# openx3.net
KiCad netlist of a schematic drawn in EAGLE
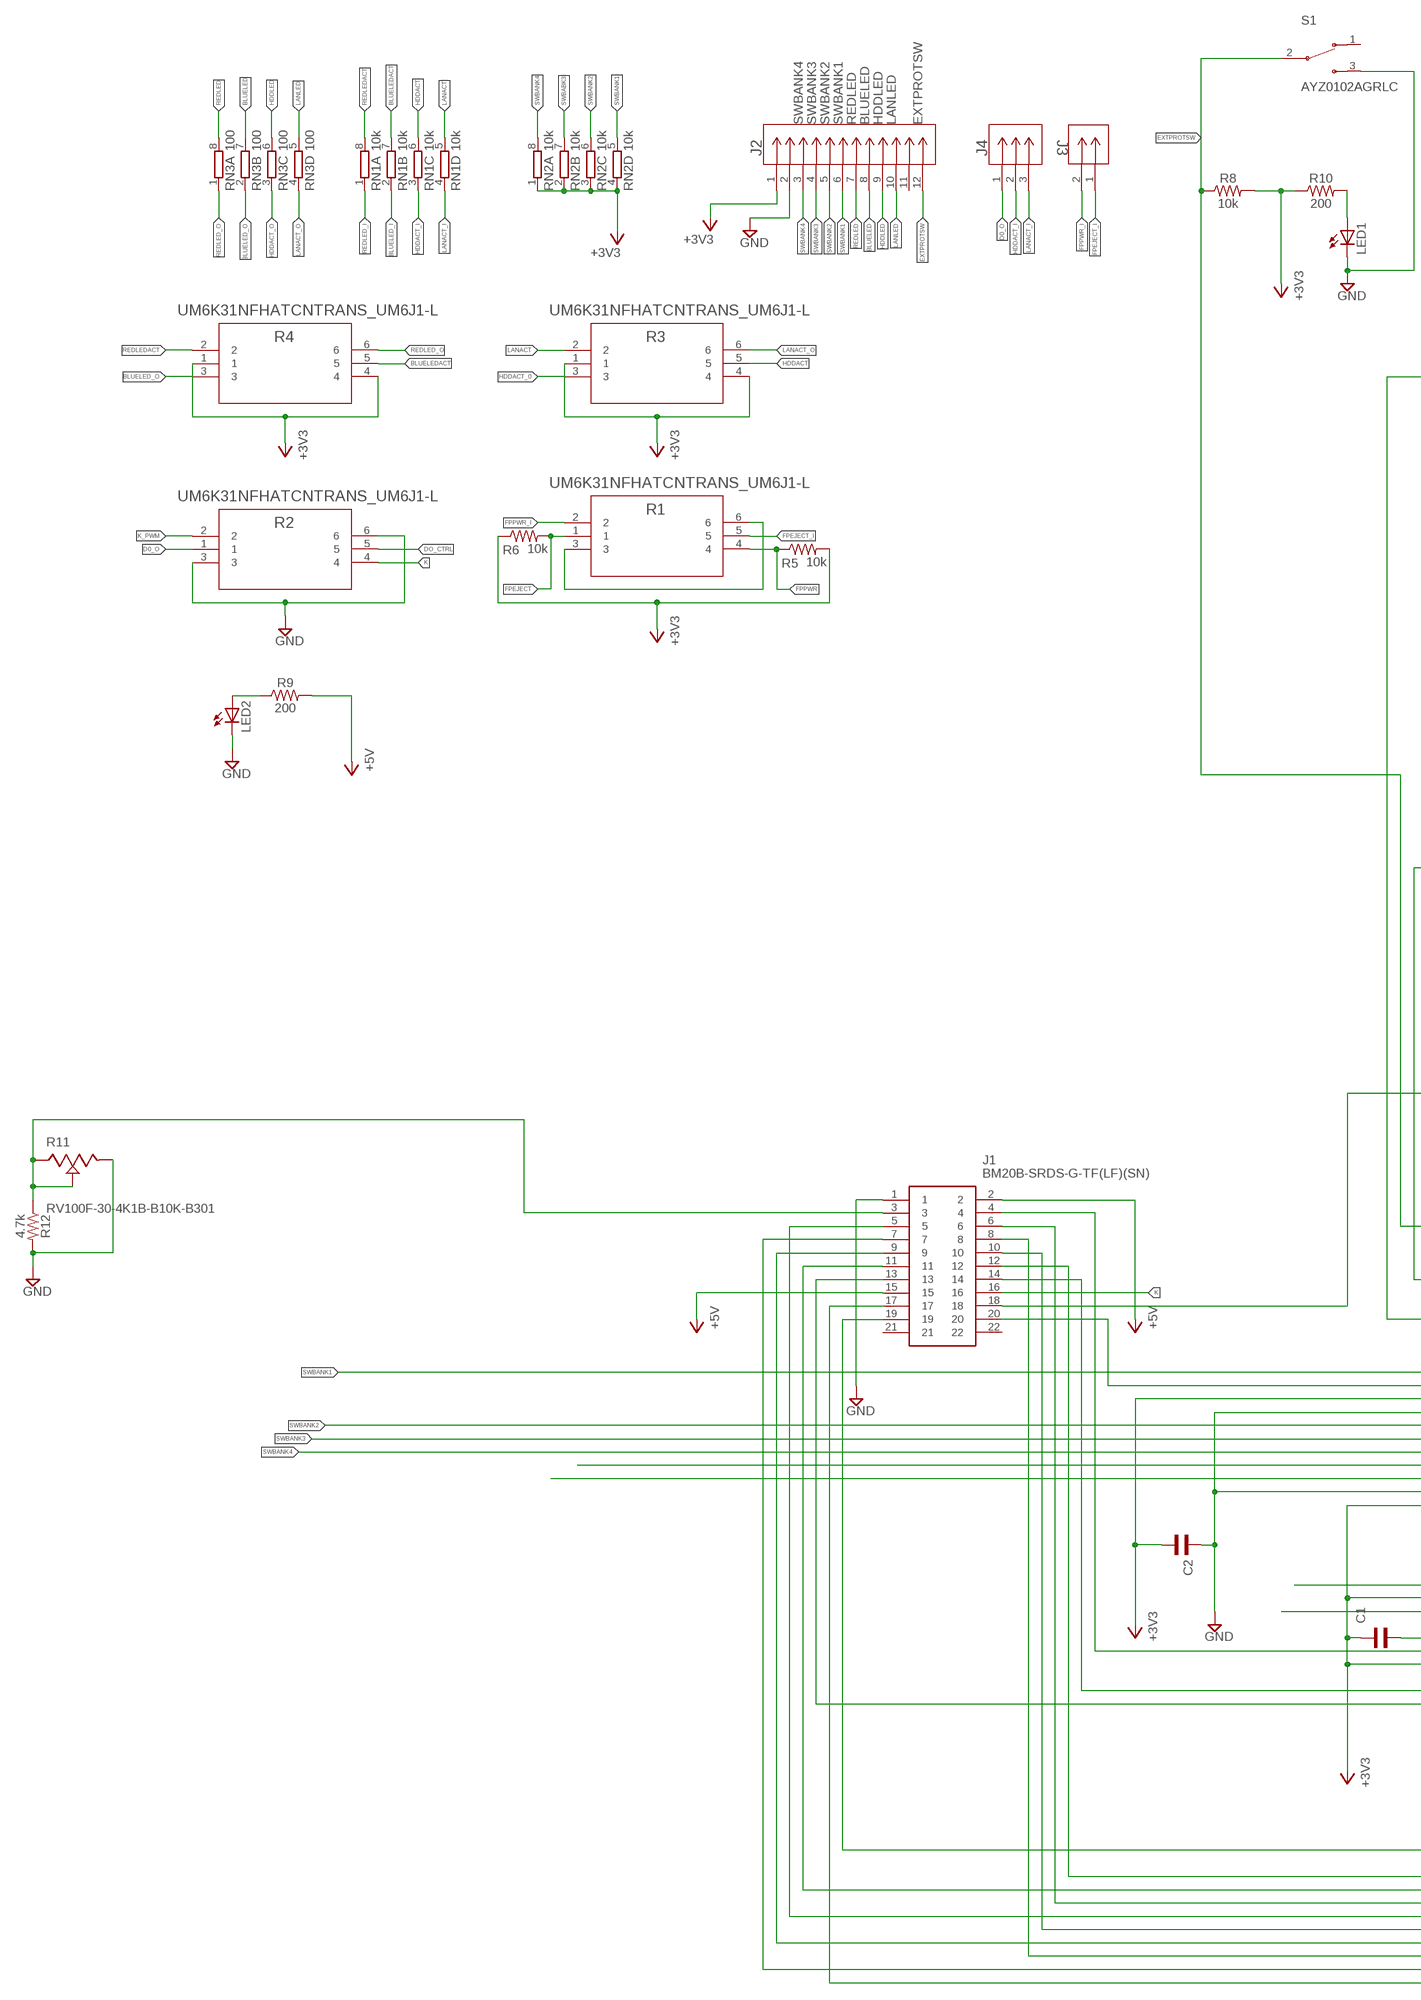
[diagram p0: schematic, sheet 1, part 1 of 2]
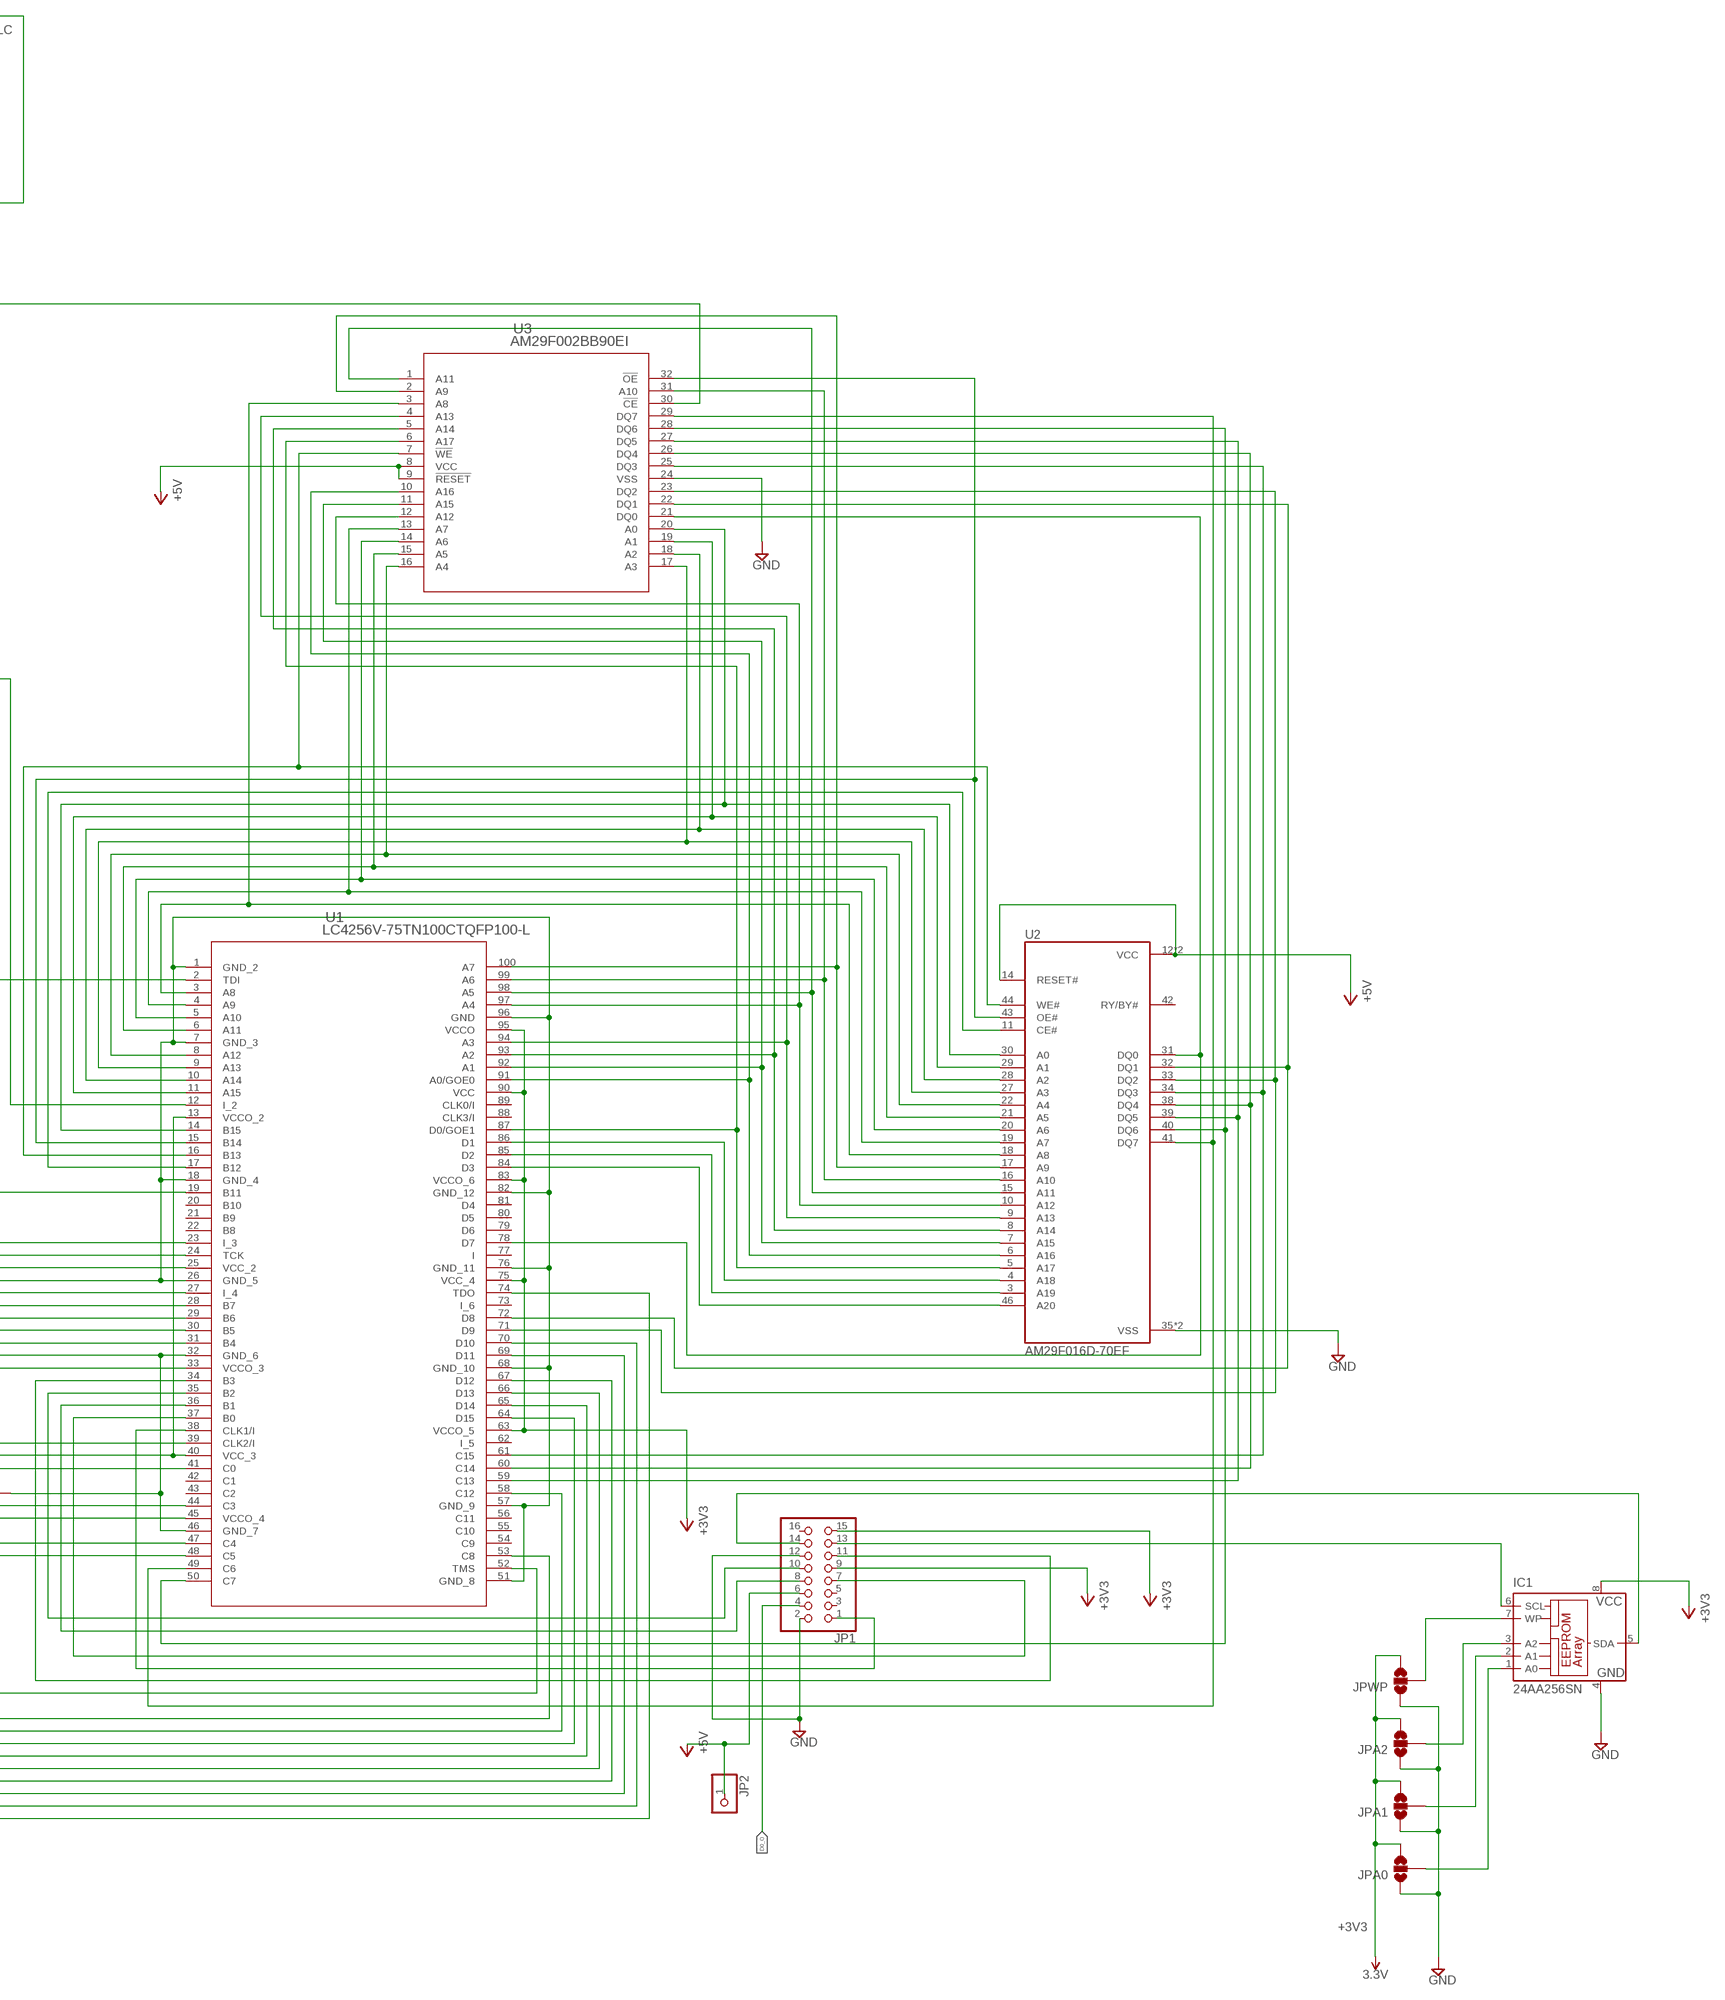
[diagram p1: schematic, sheet 1, part 2 of 2]

(export (version "E")
  (design (tool "Eeschema 10.0.6"))
  (components
    (comp (ref "C1")
      (value "WCAP-CSGP_0603_885012006001_REFLOW")
      (footprint "eagle-import:WCAP-CSGP_0603_REFLOW")
      (libsource (lib "eagle-import") (part "WCAP-CSGP_0603_REFLOW_885012006001"))
    )
    (comp (ref "C2")
      (value "WCAP-CSGP_0603_885012006001_REFLOW")
      (footprint "eagle-import:WCAP-CSGP_0603_REFLOW")
      (libsource (lib "eagle-import") (part "WCAP-CSGP_0603_REFLOW_885012006001"))
    )
    (comp (ref "IC1")
      (value "24AA256SN")
      (footprint "eagle-import:SO-08")
      (fields (field (name "MPN") "24AA256T-I/SM"))
      (libsource (lib "eagle-import") (part "24SNAA256"))
    )
    (comp (ref "J1")
      (value "BM20B-SRDS-G-TF(LF)(SN)")
      (footprint "eagle-import:BM20BSRDSGTFLFSN")
      (libsource (lib "eagle-import") (part "BM20B-SRDS-G-TF(LF)(SN)"))
    )
    (comp (ref "J2")
      (value "SM12B-SRSS-TB(LF)(SN)")
      (footprint "eagle-import:CONN_SM12B-SRSS-TB(LF)(SN)")
      (fields (field (name "COPYRIGHT") "Copyright (C) 2018 Accelerated Designs. All rights reserved"))
      (libsource (lib "eagle-import") (part "SM12B-SRSS-TB(LF)(SN)"))
    )
    (comp (ref "J3")
      (value "53398-0271")
      (footprint "eagle-import:CON00327_2")
      (fields (field (name "COPYRIGHT") "Copyright (C) 2016 Accelerated Designs. All rights reserved"))
      (libsource (lib "eagle-import") (part "53398-0271"))
    )
    (comp (ref "J4")
      (value "1734260-3")
      (footprint "eagle-import:CON3_1X3_DRM125_HPI")
      (libsource (lib "eagle-import") (part "1734260-3"))
    )
    (comp (ref "JP1")
      (value "PINHD-2X8")
      (footprint "eagle-import:2X08")
      (libsource (lib "eagle-import") (part "PINHD-2X8"))
    )
    (comp (ref "JP2")
      (value "PINHD-1X1")
      (footprint "eagle-import:1X01")
      (libsource (lib "eagle-import") (part "PINHD-1X1"))
    )
    (comp (ref "JPA0")
      (value "JUMPER-SMT_3_NO_NO-SILK")
      (footprint "eagle-import:SMT-JUMPER_3_NO_NO-SILK")
      (libsource (lib "eagle-import") (part "JUMPER-SMT_3_NO_NO-SILK"))
    )
    (comp (ref "JPA1")
      (value "JUMPER-SMT_3_NO_NO-SILK")
      (footprint "eagle-import:SMT-JUMPER_3_NO_NO-SILK")
      (libsource (lib "eagle-import") (part "JUMPER-SMT_3_NO_NO-SILK"))
    )
    (comp (ref "JPA2")
      (value "JUMPER-SMT_3_NO_NO-SILK")
      (footprint "eagle-import:SMT-JUMPER_3_NO_NO-SILK")
      (libsource (lib "eagle-import") (part "JUMPER-SMT_3_NO_NO-SILK"))
    )
    (comp (ref "JPWP")
      (value "JUMPER-SMT_3_NO_NO-SILK")
      (footprint "eagle-import:SMT-JUMPER_3_NO_NO-SILK")
      (libsource (lib "eagle-import") (part "JUMPER-SMT_3_NO_NO-SILK"))
    )
    (comp (ref "LED1")
      (value "LEDCHIPLED_0805")
      (footprint "eagle-import:CHIPLED_0805")
      (libsource (lib "eagle-import") (part "LEDCHIPLED_0805"))
    )
    (comp (ref "LED2")
      (value "LEDCHIPLED_0805")
      (footprint "eagle-import:CHIPLED_0805")
      (libsource (lib "eagle-import") (part "LEDCHIPLED_0805"))
    )
    (comp (ref "R1")
      (value "UM6K31NFHATCNTRANS_UM6J1-L")
      (footprint "eagle-import:TRANS_UM6J1-L")
      (fields
        (field (name "MANUFACTURER_PART_NUMBER") "UM6K31NFHATCN")
        (field (name "COPYRIGHT") "Copyright (C) 2018 Accelerated Designs. All rights reserved")
      )
      (libsource (lib "eagle-import") (part "UM6K31NFHATCNTRANS_UM6J1-L"))
    )
    (comp (ref "R2")
      (value "UM6K31NFHATCNTRANS_UM6J1-L")
      (footprint "eagle-import:TRANS_UM6J1-L")
      (fields
        (field (name "MANUFACTURER_PART_NUMBER") "UM6K31NFHATCN")
        (field (name "COPYRIGHT") "Copyright (C) 2018 Accelerated Designs. All rights reserved")
      )
      (libsource (lib "eagle-import") (part "UM6K31NFHATCNTRANS_UM6J1-L"))
    )
    (comp (ref "R3")
      (value "UM6K31NFHATCNTRANS_UM6J1-L")
      (footprint "eagle-import:TRANS_UM6J1-L")
      (fields
        (field (name "MANUFACTURER_PART_NUMBER") "UM6K31NFHATCN")
        (field (name "COPYRIGHT") "Copyright (C) 2018 Accelerated Designs. All rights reserved")
      )
      (libsource (lib "eagle-import") (part "UM6K31NFHATCNTRANS_UM6J1-L"))
    )
    (comp (ref "R4")
      (value "UM6K31NFHATCNTRANS_UM6J1-L")
      (footprint "eagle-import:TRANS_UM6J1-L")
      (fields
        (field (name "MANUFACTURER_PART_NUMBER") "UM6K31NFHATCN")
        (field (name "COPYRIGHT") "Copyright (C) 2018 Accelerated Designs. All rights reserved")
      )
      (libsource (lib "eagle-import") (part "UM6K31NFHATCNTRANS_UM6J1-L"))
    )
    (comp (ref "R5")
      (value "10k")
      (footprint "eagle-import:0603")
      (libsource (lib "eagle-import") (part "10KOHM-0603-1/10W-1%"))
    )
    (comp (ref "R6")
      (value "10k")
      (footprint "eagle-import:0603")
      (libsource (lib "eagle-import") (part "10KOHM-0603-1/10W-1%"))
    )
    (comp (ref "R8")
      (value "10k")
      (footprint "eagle-import:0603")
      (libsource (lib "eagle-import") (part "10KOHM-0603-1/10W-1%"))
    )
    (comp (ref "R9")
      (value "200")
      (footprint "eagle-import:0603")
      (libsource (lib "eagle-import") (part "200OHM-0603-1/10W-1%"))
    )
    (comp (ref "R10")
      (value "200")
      (footprint "eagle-import:0603")
      (libsource (lib "eagle-import") (part "200OHM-0603-1/10W-1%"))
    )
    (comp (ref "R11")
      (value "RV100F-30-4K1B-B10K-B301")
      (footprint "eagle-import:TRIM_RV100F-30-4K1B-B10K-B301")
      (fields (field (name "MF") "Alpha Taiwan"))
      (libsource (lib "eagle-import") (part "RV100F-30-4K1B-B10K-B301"))
    )
    (comp (ref "R12")
      (value "4.7k")
      (footprint "eagle-import:0603")
      (libsource (lib "eagle-import") (part "4.7KOHM-0603-1/10W-1%"))
    )
    (comp (ref "RN1")
      (value "10k")
      (footprint "eagle-import:0603-ARV")
      (libsource (lib "eagle-import") (part "4R-N0603-ARV"))
    )
    (comp (ref "RN2")
      (value "10k")
      (footprint "eagle-import:0603-ARV")
      (libsource (lib "eagle-import") (part "4R-N0603-ARV"))
    )
    (comp (ref "RN3")
      (value "100")
      (footprint "eagle-import:0603-ARV")
      (libsource (lib "eagle-import") (part "4R-N0603-ARV"))
    )
    (comp (ref "S1")
      (value "AYZ0102AGRLC")
      (footprint "eagle-import:SW_AYZ0102AGRLC")
      (fields (field (name "MF") "C&K"))
      (libsource (lib "eagle-import") (part "AYZ0102AGRLC"))
    )
    (comp (ref "U1")
      (value "LC4256V-75TN100CTQFP100-L")
      (footprint "eagle-import:TQFP100-L")
      (fields (field (name "MANUFACTURER_PART_NUMBER") "LC4256V-75TN100C"))
      (libsource (lib "eagle-import") (part "LC4256V-75TN100CTQFP100-L"))
    )
    (comp (ref "U2")
      (value "AM29F016D-70EF")
      (footprint "eagle-import:SOP50P2000X120-48N")
      (fields (field (name "MF") "Spansion"))
      (libsource (lib "eagle-import") (part "AM29F016D-70EF"))
    )
    (comp (ref "U3")
      (value "AM29F002BB90EI")
      (footprint "eagle-import:TS032")
      (libsource (lib "eagle-import") (part "AM29F002BB90EI"))
    )
  )
  (nets
    (net (code "1") (name "+3V3") (class "Default")
      (node (ref "C1") (pin "2") (pinfunction "2_2") (pintype "passive"))
      (node (ref "C2") (pin "1") (pinfunction "1_1") (pintype "passive"))
      (node (ref "IC1") (pin "8") (pinfunction "VCC_8") (pintype "power_in"))
      (node (ref "J2") (pin "1") (pinfunction "1_1") (pintype "passive"))
      (node (ref "JP1") (pin "15") (pinfunction "15_15") (pintype "passive"))
      (node (ref "JP1") (pin "9") (pinfunction "9_9") (pintype "passive"))
      (node (ref "JPA0") (pin "3") (pinfunction "3_3") (pintype "passive"))
      (node (ref "JPA1") (pin "3") (pinfunction "3_3") (pintype "passive"))
      (node (ref "JPA2") (pin "3") (pinfunction "3_3") (pintype "passive"))
      (node (ref "JPWP") (pin "3") (pinfunction "3_3") (pintype "passive"))
      (node (ref "R10") (pin "1") (pinfunction "1_1") (pintype "passive"))
      (node (ref "R3") (pin "1") (pinfunction "1_1") (pintype "passive"))
      (node (ref "R3") (pin "4") (pinfunction "4_4") (pintype "passive"))
      (node (ref "R4") (pin "1") (pinfunction "1_1") (pintype "passive"))
      (node (ref "R4") (pin "4") (pinfunction "4_4") (pintype "passive"))
      (node (ref "R5") (pin "2") (pinfunction "2_2") (pintype "passive"))
      (node (ref "R6") (pin "1") (pinfunction "1_1") (pintype "passive"))
      (node (ref "R8") (pin "2") (pinfunction "2_2") (pintype "passive"))
      (node (ref "RN2") (pin "1") (pinfunction "1_1") (pintype "passive"))
      (node (ref "RN2") (pin "2") (pinfunction "1_2") (pintype "passive"))
      (node (ref "RN2") (pin "3") (pinfunction "1_3") (pintype "passive"))
      (node (ref "RN2") (pin "4") (pinfunction "1_4") (pintype "passive"))
      (node (ref "U1") (pin "13") (pinfunction "VCCO_2_13") (pintype "power_in"))
      (node (ref "U1") (pin "25") (pinfunction "VCC_2_25") (pintype "power_in"))
      (node (ref "U1") (pin "33") (pinfunction "VCCO_3_33") (pintype "power_in"))
      (node (ref "U1") (pin "40") (pinfunction "VCC_3_40") (pintype "power_in"))
      (node (ref "U1") (pin "45") (pinfunction "VCCO_4_45") (pintype "power_in"))
      (node (ref "U1") (pin "63") (pinfunction "VCCO_5_63") (pintype "power_in"))
      (node (ref "U1") (pin "75") (pinfunction "VCC_4_75") (pintype "power_in"))
      (node (ref "U1") (pin "83") (pinfunction "VCCO_6_83") (pintype "power_in"))
      (node (ref "U1") (pin "90") (pinfunction "VCC_90") (pintype "power_in"))
      (node (ref "U1") (pin "95") (pinfunction "VCCO_95") (pintype "power_in"))
    )
    (net (code "2") (name "+5V") (class "Default")
      (node (ref "J1") (pin "15") (pinfunction "15_15") (pintype "bidirectional"))
      (node (ref "J1") (pin "2") (pinfunction "2_2") (pintype "bidirectional"))
      (node (ref "JP1") (pin "6") (pinfunction "6_6") (pintype "passive"))
      (node (ref "JP2") (pin "1") (pinfunction "1_1") (pintype "passive"))
      (node (ref "R9") (pin "2") (pinfunction "2_2") (pintype "passive"))
      (node (ref "U2") (pin "12") (pinfunction "VCC_12") (pintype "power_in"))
      (node (ref "U2") (pin "14") (pinfunction "RESET#_14") (pintype "input"))
      (node (ref "U2") (pin "37") (pinfunction "VCC_37") (pintype "power_in"))
      (node (ref "U3") (pin "8") (pinfunction "VCC_8") (pintype "power_in"))
      (node (ref "U3") (pin "9") (pinfunction "~{RESET}_9") (pintype "input"))
    )
    (net (code "3") (name "BLUELED") (class "Default")
      (node (ref "J2") (pin "8") (pinfunction "8_8") (pintype "passive"))
      (node (ref "RN3") (pin "7") (pinfunction "2_7") (pintype "passive"))
    )
    (net (code "4") (name "BLUELEDACT") (class "Default")
      (node (ref "R4") (pin "5") (pinfunction "5_5") (pintype "passive"))
      (node (ref "RN1") (pin "7") (pinfunction "2_7") (pintype "passive"))
    )
    (net (code "5") (name "BLUELED_I") (class "Default")
      (node (ref "RN1") (pin "2") (pinfunction "1_2") (pintype "passive"))
    )
    (net (code "6") (name "BLUELED_O") (class "Default")
      (node (ref "R4") (pin "3") (pinfunction "3_3") (pintype "passive"))
      (node (ref "RN3") (pin "2") (pinfunction "1_2") (pintype "passive"))
    )
    (net (code "7") (name "D0_O") (class "Default")
      (node (ref "J4") (pin "1") (pinfunction "1_1") (pintype "passive"))
      (node (ref "JP1") (pin "4") (pinfunction "4_4") (pintype "passive"))
      (node (ref "R2") (pin "1") (pinfunction "1_1") (pintype "passive"))
    )
    (net (code "8") (name "DO_CTRL") (class "Default")
      (node (ref "R2") (pin "5") (pinfunction "5_5") (pintype "passive"))
    )
    (net (code "9") (name "EXTPROTSW") (class "Default")
      (node (ref "J2") (pin "12") (pinfunction "12_12") (pintype "passive"))
      (node (ref "R8") (pin "1") (pinfunction "1_1") (pintype "passive"))
      (node (ref "S1") (pin "2") (pinfunction "2_2") (pintype "passive"))
      (node (ref "U1") (pin "12") (pinfunction "I_2_12") (pintype "passive"))
    )
    (net (code "10") (name "FPEJECT") (class "Default")
      (node (ref "R1") (pin "1") (pinfunction "1_1") (pintype "passive"))
      (node (ref "R6") (pin "2") (pinfunction "2_2") (pintype "passive"))
    )
    (net (code "11") (name "FPEJECT_I") (class "Default")
      (node (ref "J3") (pin "1") (pinfunction "1_1") (pintype "passive"))
      (node (ref "R1") (pin "5") (pinfunction "5_5") (pintype "passive"))
    )
    (net (code "12") (name "FPPWR") (class "Default")
      (node (ref "R1") (pin "4") (pinfunction "4_4") (pintype "passive"))
      (node (ref "R5") (pin "1") (pinfunction "1_1") (pintype "passive"))
    )
    (net (code "13") (name "FPPWR_I") (class "Default")
      (node (ref "J3") (pin "2") (pinfunction "2_2") (pintype "passive"))
      (node (ref "R1") (pin "2") (pinfunction "2_2") (pintype "passive"))
    )
    (net (code "14") (name "GND") (class "Default")
      (node (ref "C1") (pin "1") (pinfunction "1_1") (pintype "passive"))
      (node (ref "C2") (pin "2") (pinfunction "2_2") (pintype "passive"))
      (node (ref "IC1") (pin "4") (pinfunction "GND_4") (pintype "power_in"))
      (node (ref "J1") (pin "1") (pinfunction "1_1") (pintype "bidirectional"))
      (node (ref "J2") (pin "2") (pinfunction "2_2") (pintype "passive"))
      (node (ref "JP1") (pin "12") (pinfunction "12_12") (pintype "passive"))
      (node (ref "JP1") (pin "2") (pinfunction "2_2") (pintype "passive"))
      (node (ref "JPA0") (pin "1") (pinfunction "1_1") (pintype "passive"))
      (node (ref "JPA1") (pin "1") (pinfunction "1_1") (pintype "passive"))
      (node (ref "JPA2") (pin "1") (pinfunction "1_1") (pintype "passive"))
      (node (ref "JPWP") (pin "1") (pinfunction "1_1") (pintype "passive"))
      (node (ref "LED1") (pin "C") (pinfunction "C_C") (pintype "passive"))
      (node (ref "LED2") (pin "C") (pinfunction "C_C") (pintype "passive"))
      (node (ref "R11") (pin "3") (pinfunction "3_3") (pintype "passive"))
      (node (ref "R12") (pin "2") (pinfunction "2_2") (pintype "passive"))
      (node (ref "R2") (pin "3") (pinfunction "3_3") (pintype "passive"))
      (node (ref "R2") (pin "6") (pinfunction "6_6") (pintype "passive"))
      (node (ref "S1") (pin "3") (pinfunction "3_3") (pintype "passive"))
      (node (ref "U1") (pin "1") (pinfunction "GND_2_1") (pintype "power_in"))
      (node (ref "U1") (pin "18") (pinfunction "GND_4_18") (pintype "power_in"))
      (node (ref "U1") (pin "26") (pinfunction "GND_5_26") (pintype "power_in"))
      (node (ref "U1") (pin "32") (pinfunction "GND_6_32") (pintype "power_in"))
      (node (ref "U1") (pin "46") (pinfunction "GND_7_46") (pintype "power_in"))
      (node (ref "U1") (pin "51") (pinfunction "GND_8_51") (pintype "power_in"))
      (node (ref "U1") (pin "57") (pinfunction "GND_9_57") (pintype "power_in"))
      (node (ref "U1") (pin "68") (pinfunction "GND_10_68") (pintype "power_in"))
      (node (ref "U1") (pin "7") (pinfunction "GND_3_7") (pintype "power_in"))
      (node (ref "U1") (pin "76") (pinfunction "GND_11_76") (pintype "power_in"))
      (node (ref "U1") (pin "82") (pinfunction "GND_12_82") (pintype "power_in"))
      (node (ref "U1") (pin "96") (pinfunction "GND_96") (pintype "power_in"))
      (node (ref "U2") (pin "35") (pinfunction "VSS_35") (pintype "power_in"))
      (node (ref "U2") (pin "36") (pinfunction "VSS_36") (pintype "power_in"))
      (node (ref "U3") (pin "24") (pinfunction "VSS_24") (pintype "power_in"))
    )
    (net (code "15") (name "HDDACT") (class "Default")
      (node (ref "R3") (pin "5") (pinfunction "5_5") (pintype "passive"))
      (node (ref "RN1") (pin "6") (pinfunction "2_6") (pintype "passive"))
    )
    (net (code "16") (name "HDDACT_0") (class "Default")
      (node (ref "R3") (pin "3") (pinfunction "3_3") (pintype "passive"))
    )
    (net (code "17") (name "HDDACT_I") (class "Default")
      (node (ref "J4") (pin "2") (pinfunction "2_2") (pintype "passive"))
      (node (ref "RN1") (pin "3") (pinfunction "1_3") (pintype "passive"))
    )
    (net (code "18") (name "HDDACT_O") (class "Default")
      (node (ref "RN3") (pin "3") (pinfunction "1_3") (pintype "passive"))
    )
    (net (code "19") (name "HDDLED") (class "Default")
      (node (ref "J2") (pin "9") (pinfunction "9_9") (pintype "passive"))
      (node (ref "RN3") (pin "6") (pinfunction "2_6") (pintype "passive"))
    )
    (net (code "20") (name "K") (class "Default")
      (node (ref "J1") (pin "16") (pinfunction "16_16") (pintype "bidirectional"))
      (node (ref "R2") (pin "4") (pinfunction "4_4") (pintype "passive"))
    )
    (net (code "21") (name "K_PWM") (class "Default")
      (node (ref "R2") (pin "2") (pinfunction "2_2") (pintype "passive"))
    )
    (net (code "22") (name "LANACT") (class "Default")
      (node (ref "R3") (pin "2") (pinfunction "2_2") (pintype "passive"))
      (node (ref "RN1") (pin "5") (pinfunction "2_5") (pintype "passive"))
    )
    (net (code "23") (name "LANACT_I") (class "Default")
      (node (ref "J4") (pin "3") (pinfunction "3_3") (pintype "passive"))
      (node (ref "RN1") (pin "4") (pinfunction "1_4") (pintype "passive"))
    )
    (net (code "24") (name "LANACT_O") (class "Default")
      (node (ref "R3") (pin "6") (pinfunction "6_6") (pintype "passive"))
      (node (ref "RN3") (pin "4") (pinfunction "1_4") (pintype "passive"))
    )
    (net (code "25") (name "LANLED") (class "Default")
      (node (ref "J2") (pin "10") (pinfunction "10_10") (pintype "passive"))
      (node (ref "RN3") (pin "5") (pinfunction "2_5") (pintype "passive"))
    )
    (net (code "26") (name "Net-(IC1-A0)") (class "Default")
      (node (ref "IC1") (pin "1") (pinfunction "A0_1") (pintype "input"))
      (node (ref "JPA0") (pin "2") (pinfunction "2_2") (pintype "passive"))
    )
    (net (code "27") (name "Net-(IC1-A1)") (class "Default")
      (node (ref "IC1") (pin "2") (pinfunction "A1_2") (pintype "input"))
      (node (ref "JPA1") (pin "2") (pinfunction "2_2") (pintype "passive"))
    )
    (net (code "28") (name "Net-(IC1-A2)") (class "Default")
      (node (ref "IC1") (pin "3") (pinfunction "A2_3") (pintype "input"))
      (node (ref "JPA2") (pin "2") (pinfunction "2_2") (pintype "passive"))
    )
    (net (code "29") (name "Net-(IC1-SCL)") (class "Default")
      (node (ref "IC1") (pin "6") (pinfunction "SCL_6") (pintype "input"))
      (node (ref "JP1") (pin "13") (pinfunction "13_13") (pintype "passive"))
    )
    (net (code "30") (name "Net-(IC1-SDA)") (class "Default")
      (node (ref "IC1") (pin "5") (pinfunction "SDA_5") (pintype "bidirectional"))
      (node (ref "JP1") (pin "14") (pinfunction "14_14") (pintype "passive"))
    )
    (net (code "31") (name "Net-(IC1-WP)") (class "Default")
      (node (ref "IC1") (pin "7") (pinfunction "WP_7") (pintype "input"))
      (node (ref "JPWP") (pin "2") (pinfunction "2_2") (pintype "passive"))
    )
    (net (code "32") (name "Net-(J1-Pad3)") (class "Default")
      (node (ref "J1") (pin "3") (pinfunction "3_3") (pintype "bidirectional"))
      (node (ref "R11") (pin "1") (pinfunction "1_1") (pintype "passive"))
      (node (ref "R11") (pin "2") (pinfunction "2_2") (pintype "passive"))
      (node (ref "R12") (pin "1") (pinfunction "1_1") (pintype "passive"))
    )
    (net (code "33") (name "Net-(LED1-PadA)") (class "Default")
      (node (ref "LED1") (pin "A") (pinfunction "A_A") (pintype "passive"))
      (node (ref "R10") (pin "2") (pinfunction "2_2") (pintype "passive"))
    )
    (net (code "34") (name "Net-(LED2-PadA)") (class "Default")
      (node (ref "LED2") (pin "A") (pinfunction "A_A") (pintype "passive"))
      (node (ref "R9") (pin "1") (pinfunction "1_1") (pintype "passive"))
    )
    (net (code "35") (name "Net-(R1-Pad3)") (class "Default")
      (node (ref "R1") (pin "3") (pinfunction "3_3") (pintype "passive"))
      (node (ref "R1") (pin "6") (pinfunction "6_6") (pintype "passive"))
    )
    (net (code "36") (name "Net-(U1-A0{slash}GOE0)") (class "Default")
      (node (ref "U1") (pin "91") (pinfunction "A0/GOE0_91") (pintype "passive"))
      (node (ref "U2") (pin "6") (pinfunction "A16_6") (pintype "input"))
      (node (ref "U3") (pin "10") (pinfunction "A16_10") (pintype "input"))
    )
    (net (code "37") (name "Net-(U1-A1)") (class "Default")
      (node (ref "U1") (pin "92") (pinfunction "A1_92") (pintype "passive"))
      (node (ref "U2") (pin "7") (pinfunction "A15_7") (pintype "input"))
      (node (ref "U3") (pin "11") (pinfunction "A15_11") (pintype "input"))
    )
    (net (code "38") (name "Net-(U1-A2)") (class "Default")
      (node (ref "U1") (pin "93") (pinfunction "A2_93") (pintype "passive"))
      (node (ref "U2") (pin "8") (pinfunction "A14_8") (pintype "input"))
      (node (ref "U3") (pin "5") (pinfunction "A14_5") (pintype "input"))
    )
    (net (code "39") (name "Net-(U1-A3)") (class "Default")
      (node (ref "U1") (pin "94") (pinfunction "A3_94") (pintype "passive"))
      (node (ref "U2") (pin "9") (pinfunction "A13_9") (pintype "input"))
      (node (ref "U3") (pin "4") (pinfunction "A13_4") (pintype "input"))
    )
    (net (code "40") (name "Net-(U1-A4)") (class "Default")
      (node (ref "U1") (pin "97") (pinfunction "A4_97") (pintype "passive"))
      (node (ref "U2") (pin "10") (pinfunction "A12_10") (pintype "input"))
      (node (ref "U3") (pin "12") (pinfunction "A12_12") (pintype "input"))
    )
    (net (code "41") (name "Net-(U1-A5)") (class "Default")
      (node (ref "U1") (pin "98") (pinfunction "A5_98") (pintype "passive"))
      (node (ref "U2") (pin "15") (pinfunction "A11_15") (pintype "input"))
      (node (ref "U3") (pin "1") (pinfunction "A11_1") (pintype "input"))
    )
    (net (code "42") (name "Net-(U1-A6)") (class "Default")
      (node (ref "U1") (pin "99") (pinfunction "A6_99") (pintype "passive"))
      (node (ref "U2") (pin "16") (pinfunction "A10_16") (pintype "input"))
      (node (ref "U3") (pin "31") (pinfunction "A10_31") (pintype "input"))
    )
    (net (code "43") (name "Net-(U1-A7)") (class "Default")
      (node (ref "U1") (pin "100") (pinfunction "A7_100") (pintype "passive"))
      (node (ref "U2") (pin "17") (pinfunction "A9_17") (pintype "input"))
      (node (ref "U3") (pin "2") (pinfunction "A9_2") (pintype "input"))
    )
    (net (code "44") (name "Net-(U1-A8)") (class "Default")
      (node (ref "U1") (pin "3") (pinfunction "A8_3") (pintype "passive"))
      (node (ref "U2") (pin "18") (pinfunction "A8_18") (pintype "input"))
      (node (ref "U3") (pin "3") (pinfunction "A8_3") (pintype "input"))
    )
    (net (code "45") (name "Net-(U1-A9)") (class "Default")
      (node (ref "U1") (pin "4") (pinfunction "A9_4") (pintype "passive"))
      (node (ref "U2") (pin "19") (pinfunction "A7_19") (pintype "input"))
      (node (ref "U3") (pin "13") (pinfunction "A7_13") (pintype "input"))
    )
    (net (code "46") (name "Net-(U1-A10)") (class "Default")
      (node (ref "U1") (pin "5") (pinfunction "A10_5") (pintype "passive"))
      (node (ref "U2") (pin "20") (pinfunction "A6_20") (pintype "input"))
      (node (ref "U3") (pin "14") (pinfunction "A6_14") (pintype "input"))
    )
    (net (code "47") (name "Net-(U1-A11)") (class "Default")
      (node (ref "U1") (pin "6") (pinfunction "A11_6") (pintype "passive"))
      (node (ref "U2") (pin "21") (pinfunction "A5_21") (pintype "input"))
      (node (ref "U3") (pin "15") (pinfunction "A5_15") (pintype "input"))
    )
    (net (code "48") (name "Net-(U1-A12)") (class "Default")
      (node (ref "U1") (pin "8") (pinfunction "A12_8") (pintype "passive"))
      (node (ref "U2") (pin "22") (pinfunction "A4_22") (pintype "input"))
      (node (ref "U3") (pin "16") (pinfunction "A4_16") (pintype "input"))
    )
    (net (code "49") (name "Net-(U1-A13)") (class "Default")
      (node (ref "U1") (pin "9") (pinfunction "A13_9") (pintype "passive"))
      (node (ref "U2") (pin "27") (pinfunction "A3_27") (pintype "input"))
      (node (ref "U3") (pin "17") (pinfunction "A3_17") (pintype "input"))
    )
    (net (code "50") (name "Net-(U1-A14)") (class "Default")
      (node (ref "U1") (pin "10") (pinfunction "A14_10") (pintype "passive"))
      (node (ref "U2") (pin "28") (pinfunction "A2_28") (pintype "input"))
      (node (ref "U3") (pin "18") (pinfunction "A2_18") (pintype "input"))
    )
    (net (code "51") (name "Net-(U1-A15)") (class "Default")
      (node (ref "U1") (pin "11") (pinfunction "A15_11") (pintype "passive"))
      (node (ref "U2") (pin "29") (pinfunction "A1_29") (pintype "input"))
      (node (ref "U3") (pin "19") (pinfunction "A1_19") (pintype "input"))
    )
    (net (code "52") (name "Net-(U1-B0)") (class "Default")
      (node (ref "JP1") (pin "7") (pinfunction "7_7") (pintype "passive"))
      (node (ref "U1") (pin "37") (pinfunction "B0_37") (pintype "passive"))
    )
    (net (code "53") (name "Net-(U1-B1)") (class "Default")
      (node (ref "JP1") (pin "8") (pinfunction "8_8") (pintype "passive"))
      (node (ref "U1") (pin "36") (pinfunction "B1_36") (pintype "passive"))
    )
    (net (code "54") (name "Net-(U1-B2)") (class "Default")
      (node (ref "JP1") (pin "10") (pinfunction "10_10") (pintype "passive"))
      (node (ref "U1") (pin "35") (pinfunction "B2_35") (pintype "passive"))
    )
    (net (code "55") (name "Net-(U1-B3)") (class "Default")
      (node (ref "JP1") (pin "11") (pinfunction "11_11") (pintype "passive"))
      (node (ref "U1") (pin "34") (pinfunction "B3_34") (pintype "passive"))
    )
    (net (code "56") (name "Net-(U1-B11)") (class "Default")
      (node (ref "U1") (pin "19") (pinfunction "B11_19") (pintype "passive"))
      (node (ref "U3") (pin "30") (pinfunction "~{CE}_30") (pintype "input"))
    )
    (net (code "57") (name "Net-(U1-B12)") (class "Default")
      (node (ref "U1") (pin "17") (pinfunction "B12_17") (pintype "passive"))
      (node (ref "U2") (pin "11") (pinfunction "CE#_11") (pintype "input"))
    )
    (net (code "58") (name "Net-(U1-B13)") (class "Default")
      (node (ref "U1") (pin "16") (pinfunction "B13_16") (pintype "passive"))
      (node (ref "U2") (pin "44") (pinfunction "WE#_44") (pintype "input"))
      (node (ref "U3") (pin "7") (pinfunction "~{WE}_7") (pintype "input"))
    )
    (net (code "59") (name "Net-(U1-B14)") (class "Default")
      (node (ref "U1") (pin "15") (pinfunction "B14_15") (pintype "passive"))
      (node (ref "U2") (pin "43") (pinfunction "OE#_43") (pintype "input"))
      (node (ref "U3") (pin "32") (pinfunction "~{OE}_32") (pintype "input"))
    )
    (net (code "60") (name "Net-(U1-B15)") (class "Default")
      (node (ref "U1") (pin "14") (pinfunction "B15_14") (pintype "passive"))
      (node (ref "U2") (pin "30") (pinfunction "A0_30") (pintype "input"))
      (node (ref "U3") (pin "20") (pinfunction "A0_20") (pintype "input"))
    )
    (net (code "61") (name "Net-(U1-C3)") (class "Default")
      (node (ref "J1") (pin "4") (pinfunction "4_4") (pintype "bidirectional"))
      (node (ref "U1") (pin "44") (pinfunction "C3_44") (pintype "passive"))
    )
    (net (code "62") (name "Net-(U1-C4)") (class "Default")
      (node (ref "J1") (pin "14") (pinfunction "14_14") (pintype "bidirectional"))
      (node (ref "U1") (pin "47") (pinfunction "C4_47") (pintype "passive"))
    )
    (net (code "63") (name "Net-(U1-C5)") (class "Default")
      (node (ref "J1") (pin "13") (pinfunction "13_13") (pintype "bidirectional"))
      (node (ref "U1") (pin "48") (pinfunction "C5_48") (pintype "passive"))
    )
    (net (code "64") (name "Net-(U1-C6)") (class "Default")
      (node (ref "U1") (pin "49") (pinfunction "C6_49") (pintype "passive"))
      (node (ref "U2") (pin "41") (pinfunction "DQ7_41") (pintype "bidirectional"))
      (node (ref "U3") (pin "29") (pinfunction "DQ7_29") (pintype "bidirectional"))
    )
    (net (code "65") (name "Net-(U1-C7)") (class "Default")
      (node (ref "U1") (pin "50") (pinfunction "C7_50") (pintype "passive"))
      (node (ref "U2") (pin "40") (pinfunction "DQ6_40") (pintype "bidirectional"))
      (node (ref "U3") (pin "28") (pinfunction "DQ6_28") (pintype "bidirectional"))
    )
    (net (code "66") (name "Net-(U1-C8)") (class "Default")
      (node (ref "J1") (pin "12") (pinfunction "12_12") (pintype "bidirectional"))
      (node (ref "U1") (pin "53") (pinfunction "C8_53") (pintype "passive"))
    )
    (net (code "67") (name "Net-(U1-C12)") (class "Default")
      (node (ref "J1") (pin "11") (pinfunction "11_11") (pintype "bidirectional"))
      (node (ref "U1") (pin "58") (pinfunction "C12_58") (pintype "passive"))
    )
    (net (code "68") (name "Net-(U1-C13)") (class "Default")
      (node (ref "U1") (pin "59") (pinfunction "C13_59") (pintype "passive"))
      (node (ref "U2") (pin "39") (pinfunction "DQ5_39") (pintype "bidirectional"))
      (node (ref "U3") (pin "27") (pinfunction "DQ5_27") (pintype "bidirectional"))
    )
    (net (code "69") (name "Net-(U1-C14)") (class "Default")
      (node (ref "U1") (pin "60") (pinfunction "C14_60") (pintype "passive"))
      (node (ref "U2") (pin "38") (pinfunction "DQ4_38") (pintype "bidirectional"))
      (node (ref "U3") (pin "26") (pinfunction "DQ4_26") (pintype "bidirectional"))
    )
    (net (code "70") (name "Net-(U1-C15)") (class "Default")
      (node (ref "U1") (pin "61") (pinfunction "C15_61") (pintype "passive"))
      (node (ref "U2") (pin "34") (pinfunction "DQ3_34") (pintype "bidirectional"))
      (node (ref "U3") (pin "25") (pinfunction "DQ3_25") (pintype "bidirectional"))
    )
    (net (code "71") (name "Net-(U1-CLK1{slash}I)") (class "Default")
      (node (ref "JP1") (pin "1") (pinfunction "1_1") (pintype "passive"))
      (node (ref "U1") (pin "38") (pinfunction "CLK1/I_38") (pintype "passive"))
    )
    (net (code "72") (name "Net-(U1-D0{slash}GOE1)") (class "Default")
      (node (ref "U1") (pin "87") (pinfunction "D0/GOE1_87") (pintype "passive"))
      (node (ref "U2") (pin "5") (pinfunction "A17_5") (pintype "input"))
      (node (ref "U3") (pin "6") (pinfunction "A17_6") (pintype "input"))
    )
    (net (code "73") (name "Net-(U1-D1)") (class "Default")
      (node (ref "U1") (pin "86") (pinfunction "D1_86") (pintype "passive"))
      (node (ref "U2") (pin "4") (pinfunction "A18_4") (pintype "input"))
    )
    (net (code "74") (name "Net-(U1-D2)") (class "Default")
      (node (ref "U1") (pin "85") (pinfunction "D2_85") (pintype "passive"))
      (node (ref "U2") (pin "3") (pinfunction "A19_3") (pintype "input"))
    )
    (net (code "75") (name "Net-(U1-D3)") (class "Default")
      (node (ref "U1") (pin "84") (pinfunction "D3_84") (pintype "passive"))
      (node (ref "U2") (pin "46") (pinfunction "A20_46") (pintype "input"))
    )
    (net (code "76") (name "Net-(U1-D7)") (class "Default")
      (node (ref "U1") (pin "78") (pinfunction "D7_78") (pintype "passive"))
      (node (ref "U2") (pin "31") (pinfunction "DQ0_31") (pintype "bidirectional"))
      (node (ref "U3") (pin "21") (pinfunction "DQ0_21") (pintype "bidirectional"))
    )
    (net (code "77") (name "Net-(U1-D8)") (class "Default")
      (node (ref "U1") (pin "72") (pinfunction "D8_72") (pintype "passive"))
      (node (ref "U2") (pin "32") (pinfunction "DQ1_32") (pintype "bidirectional"))
      (node (ref "U3") (pin "22") (pinfunction "DQ1_22") (pintype "bidirectional"))
    )
    (net (code "78") (name "Net-(U1-D9)") (class "Default")
      (node (ref "U1") (pin "71") (pinfunction "D9_71") (pintype "passive"))
      (node (ref "U2") (pin "33") (pinfunction "DQ2_33") (pintype "bidirectional"))
      (node (ref "U3") (pin "23") (pinfunction "DQ2_23") (pintype "bidirectional"))
    )
    (net (code "79") (name "Net-(U1-D10)") (class "Default")
      (node (ref "J1") (pin "7") (pinfunction "7_7") (pintype "bidirectional"))
      (node (ref "U1") (pin "70") (pinfunction "D10_70") (pintype "passive"))
    )
    (net (code "80") (name "Net-(U1-D11)") (class "Default")
      (node (ref "J1") (pin "8") (pinfunction "8_8") (pintype "bidirectional"))
      (node (ref "U1") (pin "69") (pinfunction "D11_69") (pintype "passive"))
    )
    (net (code "81") (name "Net-(U1-D12)") (class "Default")
      (node (ref "J1") (pin "9") (pinfunction "9_9") (pintype "bidirectional"))
      (node (ref "U1") (pin "67") (pinfunction "D12_67") (pintype "passive"))
    )
    (net (code "82") (name "Net-(U1-D13)") (class "Default")
      (node (ref "J1") (pin "10") (pinfunction "10_10") (pintype "bidirectional"))
      (node (ref "U1") (pin "66") (pinfunction "D13_66") (pintype "passive"))
    )
    (net (code "83") (name "Net-(U1-D14)") (class "Default")
      (node (ref "J1") (pin "5") (pinfunction "5_5") (pintype "bidirectional"))
      (node (ref "U1") (pin "65") (pinfunction "D14_65") (pintype "passive"))
    )
    (net (code "84") (name "Net-(U1-D15)") (class "Default")
      (node (ref "J1") (pin "6") (pinfunction "6_6") (pintype "bidirectional"))
      (node (ref "U1") (pin "64") (pinfunction "D15_64") (pintype "passive"))
    )
    (net (code "85") (name "Net-(U1-TCK)") (class "Default")
      (node (ref "J1") (pin "20") (pinfunction "20_20") (pintype "bidirectional"))
      (node (ref "U1") (pin "24") (pinfunction "TCK_24") (pintype "passive"))
    )
    (net (code "86") (name "Net-(U1-TDI)") (class "Default")
      (node (ref "J1") (pin "18") (pinfunction "18_18") (pintype "bidirectional"))
      (node (ref "U1") (pin "2") (pinfunction "TDI_2") (pintype "passive"))
    )
    (net (code "87") (name "Net-(U1-TDO)") (class "Default")
      (node (ref "J1") (pin "17") (pinfunction "17_17") (pintype "bidirectional"))
      (node (ref "U1") (pin "74") (pinfunction "TDO_74") (pintype "passive"))
    )
    (net (code "88") (name "Net-(U1-TMS)") (class "Default")
      (node (ref "J1") (pin "19") (pinfunction "19_19") (pintype "bidirectional"))
      (node (ref "U1") (pin "52") (pinfunction "TMS_52") (pintype "passive"))
    )
    (net (code "89") (name "REDLED") (class "Default")
      (node (ref "J2") (pin "7") (pinfunction "7_7") (pintype "passive"))
      (node (ref "RN3") (pin "8") (pinfunction "2_8") (pintype "passive"))
    )
    (net (code "90") (name "REDLEDACT") (class "Default")
      (node (ref "R4") (pin "2") (pinfunction "2_2") (pintype "passive"))
      (node (ref "RN1") (pin "8") (pinfunction "2_8") (pintype "passive"))
    )
    (net (code "91") (name "REDLED_I") (class "Default")
      (node (ref "RN1") (pin "1") (pinfunction "1_1") (pintype "passive"))
    )
    (net (code "92") (name "REDLED_O") (class "Default")
      (node (ref "R4") (pin "6") (pinfunction "6_6") (pintype "passive"))
      (node (ref "RN3") (pin "1") (pinfunction "1_1") (pintype "passive"))
    )
    (net (code "93") (name "SWBABK3") (class "Default")
      (node (ref "RN2") (pin "7") (pinfunction "2_7") (pintype "passive"))
    )
    (net (code "94") (name "SWBANK1") (class "Default")
      (node (ref "J2") (pin "6") (pinfunction "6_6") (pintype "passive"))
      (node (ref "RN2") (pin "5") (pinfunction "2_5") (pintype "passive"))
      (node (ref "U1") (pin "23") (pinfunction "I_3_23") (pintype "passive"))
    )
    (net (code "95") (name "SWBANK2") (class "Default")
      (node (ref "J2") (pin "5") (pinfunction "5_5") (pintype "passive"))
      (node (ref "RN2") (pin "6") (pinfunction "2_6") (pintype "passive"))
      (node (ref "U1") (pin "27") (pinfunction "I_4_27") (pintype "passive"))
    )
    (net (code "96") (name "SWBANK3") (class "Default")
      (node (ref "J2") (pin "4") (pinfunction "4_4") (pintype "passive"))
      (node (ref "U1") (pin "28") (pinfunction "B7_28") (pintype "passive"))
    )
    (net (code "97") (name "SWBANK4") (class "Default")
      (node (ref "J2") (pin "3") (pinfunction "3_3") (pintype "passive"))
      (node (ref "RN2") (pin "8") (pinfunction "2_8") (pintype "passive"))
      (node (ref "U1") (pin "29") (pinfunction "B6_29") (pintype "passive"))
    )
    (net (code "98") (name "unconnected-(J1-Pad21)") (class "Default")
      (node (ref "J1") (pin "21") (pinfunction "21_21") (pintype "bidirectional"))
    )
    (net (code "99") (name "unconnected-(J1-Pad22)") (class "Default")
      (node (ref "J1") (pin "22") (pinfunction "22_22") (pintype "bidirectional"))
    )
    (net (code "100") (name "unconnected-(J2-Pad11)") (class "Default")
      (node (ref "J2") (pin "11") (pinfunction "11_11") (pintype "passive"))
    )
    (net (code "101") (name "unconnected-(JP1-Pad3)") (class "Default")
      (node (ref "JP1") (pin "3") (pinfunction "3_3") (pintype "passive"))
    )
    (net (code "102") (name "unconnected-(JP1-Pad5)") (class "Default")
      (node (ref "JP1") (pin "5") (pinfunction "5_5") (pintype "passive"))
    )
    (net (code "103") (name "unconnected-(JP1-Pad16)") (class "Default")
      (node (ref "JP1") (pin "16") (pinfunction "16_16") (pintype "passive"))
    )
    (net (code "104") (name "unconnected-(S1-Pad1)") (class "Default")
      (node (ref "S1") (pin "1") (pinfunction "1_1") (pintype "passive"))
    )
    (net (code "105") (name "unconnected-(U1-B4-Pad31)") (class "Default")
      (node (ref "U1") (pin "31") (pinfunction "B4_31") (pintype "passive"))
    )
    (net (code "106") (name "unconnected-(U1-B5-Pad30)") (class "Default")
      (node (ref "U1") (pin "30") (pinfunction "B5_30") (pintype "passive"))
    )
    (net (code "107") (name "unconnected-(U1-B8-Pad22)") (class "Default")
      (node (ref "U1") (pin "22") (pinfunction "B8_22") (pintype "passive"))
    )
    (net (code "108") (name "unconnected-(U1-B9-Pad21)") (class "Default")
      (node (ref "U1") (pin "21") (pinfunction "B9_21") (pintype "passive"))
    )
    (net (code "109") (name "unconnected-(U1-B10-Pad20)") (class "Default")
      (node (ref "U1") (pin "20") (pinfunction "B10_20") (pintype "passive"))
    )
    (net (code "110") (name "unconnected-(U1-C0-Pad41)") (class "Default")
      (node (ref "U1") (pin "41") (pinfunction "C0_41") (pintype "passive"))
    )
    (net (code "111") (name "unconnected-(U1-C1-Pad42)") (class "Default")
      (node (ref "U1") (pin "42") (pinfunction "C1_42") (pintype "passive"))
    )
    (net (code "112") (name "unconnected-(U1-C2-Pad43)") (class "Default")
      (node (ref "U1") (pin "43") (pinfunction "C2_43") (pintype "passive"))
    )
    (net (code "113") (name "unconnected-(U1-C9-Pad54)") (class "Default")
      (node (ref "U1") (pin "54") (pinfunction "C9_54") (pintype "passive"))
    )
    (net (code "114") (name "unconnected-(U1-C10-Pad55)") (class "Default")
      (node (ref "U1") (pin "55") (pinfunction "C10_55") (pintype "passive"))
    )
    (net (code "115") (name "unconnected-(U1-C11-Pad56)") (class "Default")
      (node (ref "U1") (pin "56") (pinfunction "C11_56") (pintype "passive"))
    )
    (net (code "116") (name "unconnected-(U1-CLK0{slash}I-Pad89)") (class "Default")
      (node (ref "U1") (pin "89") (pinfunction "CLK0/I_89") (pintype "passive"))
    )
    (net (code "117") (name "unconnected-(U1-CLK2{slash}I-Pad39)") (class "Default")
      (node (ref "U1") (pin "39") (pinfunction "CLK2/I_39") (pintype "passive"))
    )
    (net (code "118") (name "unconnected-(U1-CLK3{slash}I-Pad88)") (class "Default")
      (node (ref "U1") (pin "88") (pinfunction "CLK3/I_88") (pintype "passive"))
    )
    (net (code "119") (name "unconnected-(U1-D4-Pad81)") (class "Default")
      (node (ref "U1") (pin "81") (pinfunction "D4_81") (pintype "passive"))
    )
    (net (code "120") (name "unconnected-(U1-D5-Pad80)") (class "Default")
      (node (ref "U1") (pin "80") (pinfunction "D5_80") (pintype "passive"))
    )
    (net (code "121") (name "unconnected-(U1-D6-Pad79)") (class "Default")
      (node (ref "U1") (pin "79") (pinfunction "D6_79") (pintype "passive"))
    )
    (net (code "122") (name "unconnected-(U1-I-Pad77)") (class "Default")
      (node (ref "U1") (pin "77") (pinfunction "I_77") (pintype "passive"))
    )
    (net (code "123") (name "unconnected-(U1-I_5-Pad62)") (class "Default")
      (node (ref "U1") (pin "62") (pinfunction "I_5_62") (pintype "passive"))
    )
    (net (code "124") (name "unconnected-(U1-I_6-Pad73)") (class "Default")
      (node (ref "U1") (pin "73") (pinfunction "I_6_73") (pintype "passive"))
    )
    (net (code "125") (name "unconnected-(U2-RY{slash}BY#-Pad42)") (class "Default")
      (node (ref "U2") (pin "42") (pinfunction "RY/BY#_42") (pintype "output"))
    )
  )
)
